# ESP_SPI.net
KiCad netlist of a schematic drawn in EAGLE
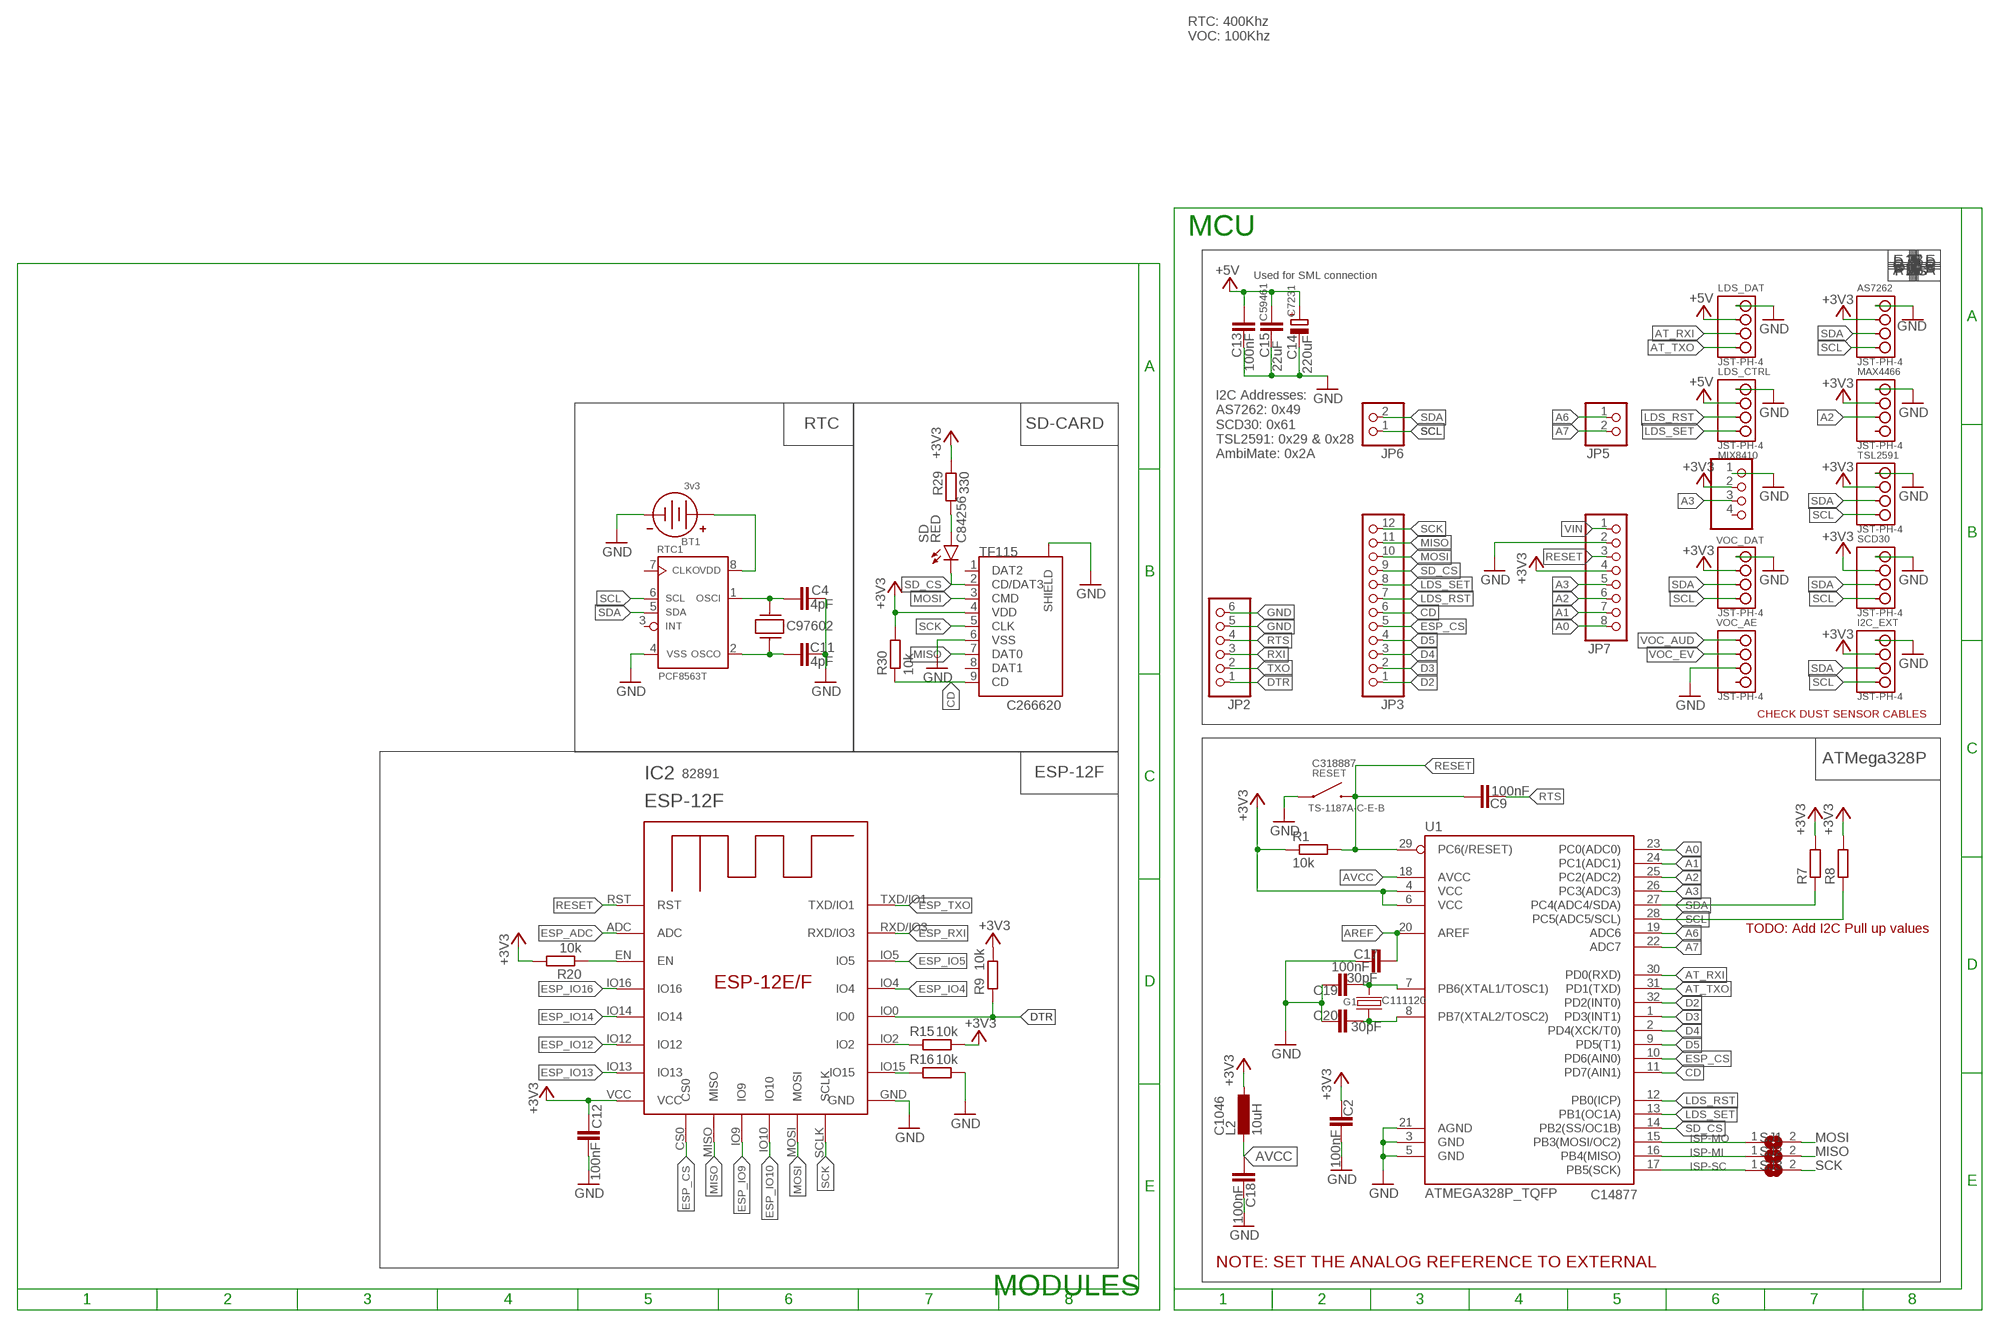
[diagram p0: schematic, sheet 1, part 1 of 2]
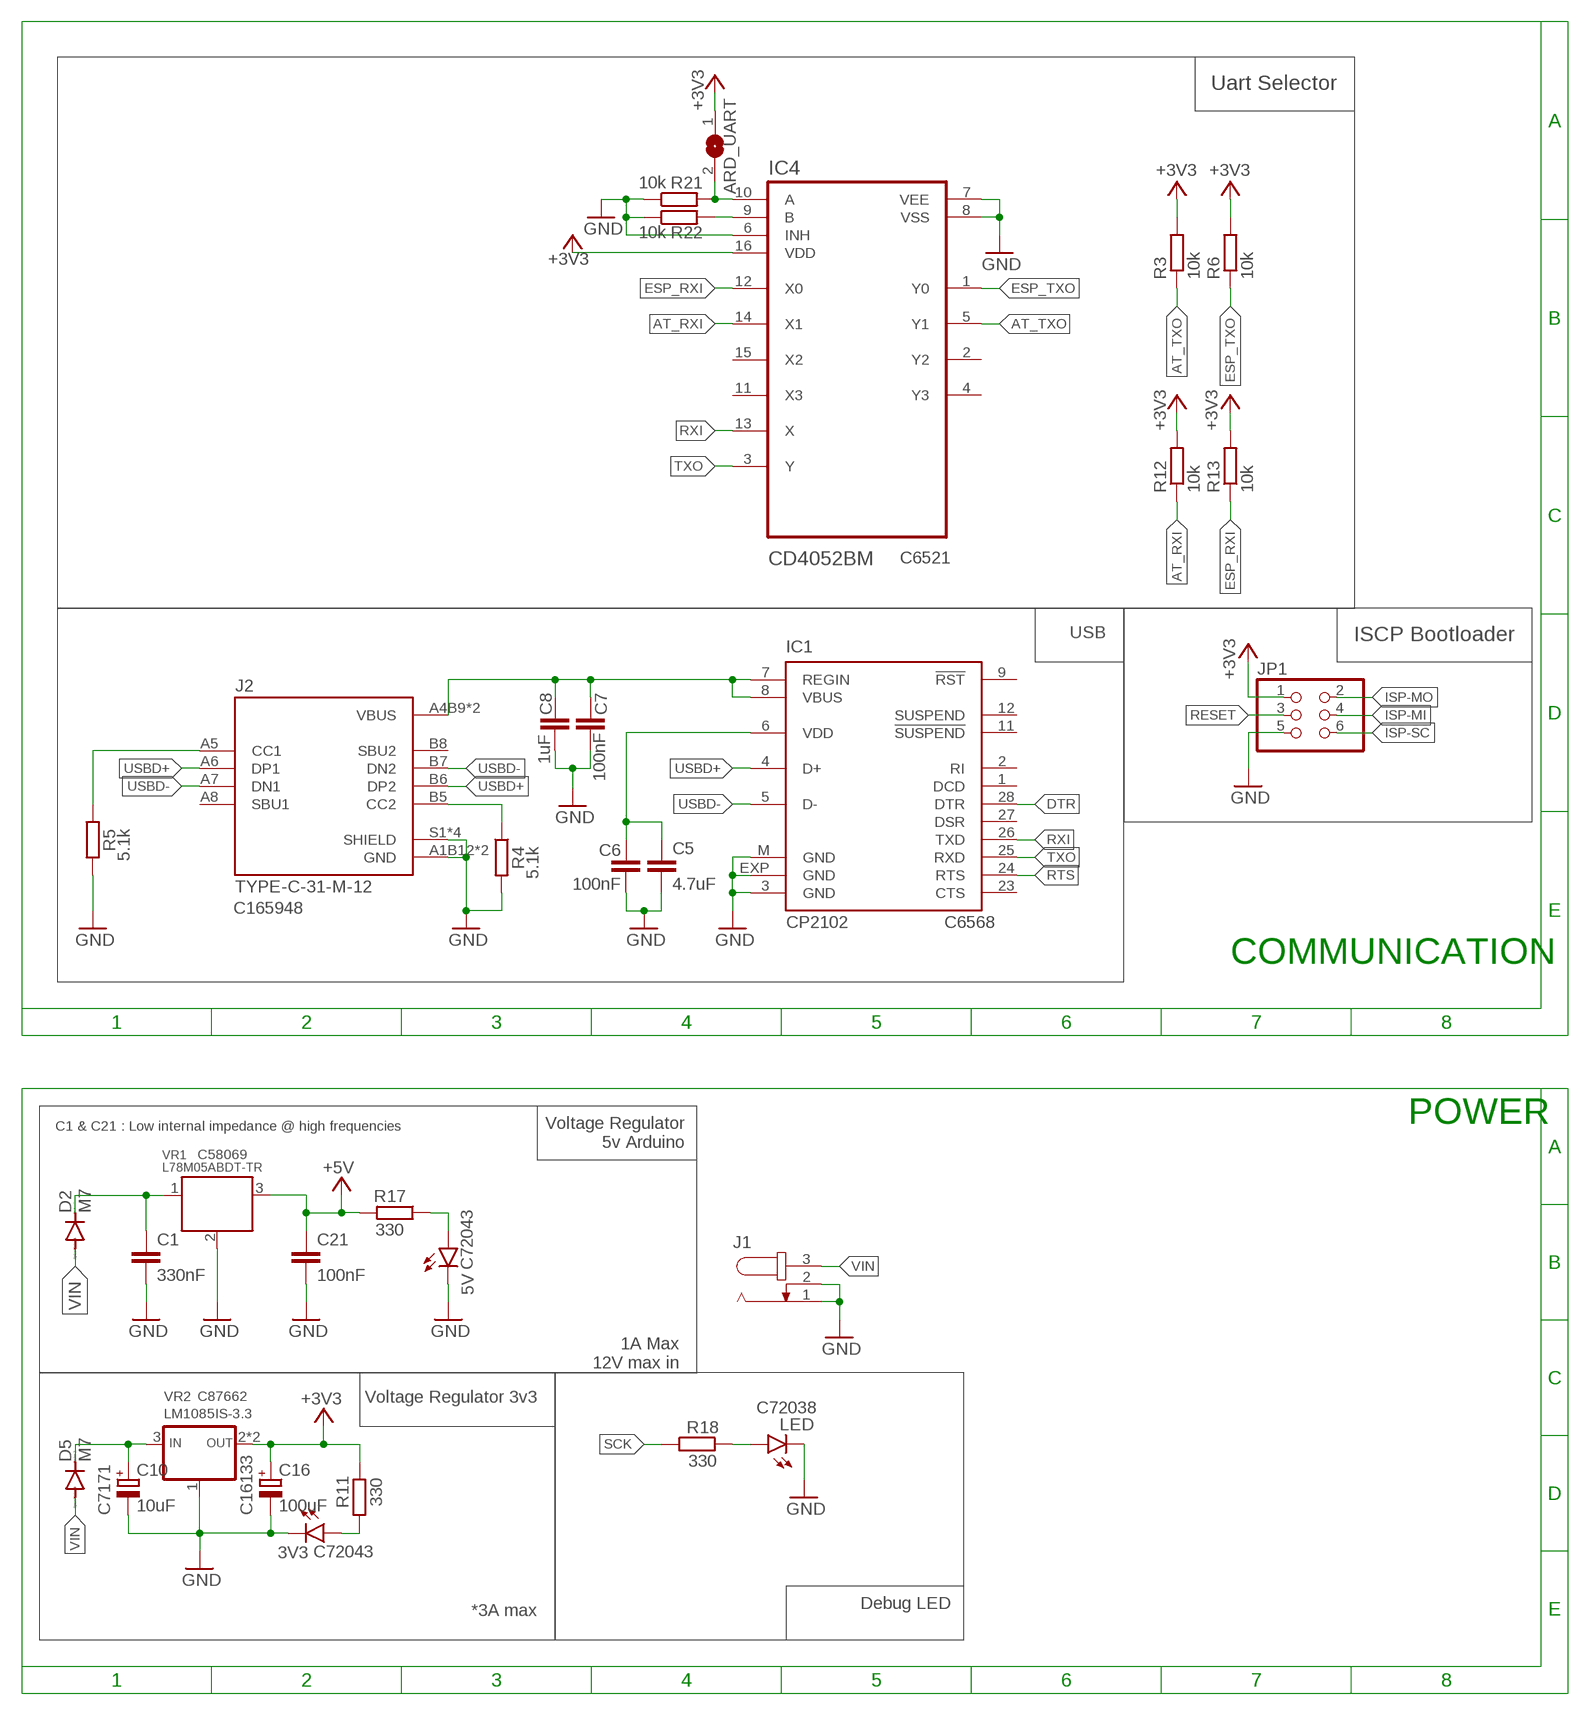
[diagram p1: schematic, sheet 1, part 2 of 2]

(export (version "E")
  (design (tool "Eeschema 10.0.6"))
  (components
    (comp (ref "3V3")
      (value "C72043")
      (footprint "eagle-import:CHIPLED_0603")
      (fields (field (name "PTNR") "C72043"))
      (libsource (lib "eagle-import") (part "LEDCHIPLED_0603"))
    )
    (comp (ref "5V")
      (value "C72043")
      (footprint "eagle-import:CHIPLED_0603")
      (fields (field (name "PTNR") "C72043"))
      (libsource (lib "eagle-import") (part "LEDCHIPLED_0603"))
    )
    (comp (ref "ARD_UART")
      (value "SJ")
      (footprint "eagle-import:SJ")
      (libsource (lib "eagle-import") (part "SJ"))
    )
    (comp (ref "AS7262")
      (value "JST-PH-4")
      (footprint "eagle-import:JST-PH-4")
      (libsource (lib "eagle-import") (part "JST-PH-4"))
    )
    (comp (ref "BT1")
      (value "3v3")
      (footprint "eagle-import:CH29-2032LF")
      (libsource (lib "eagle-import") (part "CH29-2032LF"))
    )
    (comp (ref "C1")
      (value "330nF")
      (footprint "eagle-import:C0805")
      (libsource (lib "eagle-import") (part "C-EUC0805"))
    )
    (comp (ref "C2")
      (value "100nF")
      (footprint "eagle-import:C0402")
      (libsource (lib "eagle-import") (part "C-EUC0402"))
    )
    (comp (ref "C4")
      (value "4pF")
      (footprint "eagle-import:C0402")
      (libsource (lib "eagle-import") (part "C-EUC0402"))
    )
    (comp (ref "C5")
      (value "4.7uF")
      (footprint "eagle-import:C0402")
      (libsource (lib "eagle-import") (part "C-EUC0402"))
    )
    (comp (ref "C6")
      (value "100nF")
      (footprint "eagle-import:C0402")
      (libsource (lib "eagle-import") (part "C-EUC0402"))
    )
    (comp (ref "C7")
      (value "100nF")
      (footprint "eagle-import:C0402")
      (libsource (lib "eagle-import") (part "C-EUC0402"))
    )
    (comp (ref "C8")
      (value "1uF")
      (footprint "eagle-import:C0402")
      (libsource (lib "eagle-import") (part "C-EUC0402"))
    )
    (comp (ref "C9")
      (value "100nF")
      (footprint "eagle-import:C0402")
      (libsource (lib "eagle-import") (part "C-EUC0402"))
    )
    (comp (ref "C10")
      (value "10uF")
      (footprint "eagle-import:A_3216-18R")
      (fields (field (name "PTRNR") "C7171"))
      (libsource (lib "eagle-import") (part "CPOL-EUA/3216-18R"))
    )
    (comp (ref "C11")
      (value "4pF")
      (footprint "eagle-import:C0402")
      (libsource (lib "eagle-import") (part "C-EUC0402"))
    )
    (comp (ref "C12")
      (value "100nF")
      (footprint "eagle-import:C0402")
      (libsource (lib "eagle-import") (part "C-EUC0402"))
    )
    (comp (ref "C13")
      (value "100nF")
      (footprint "eagle-import:C0402")
      (libsource (lib "eagle-import") (part "C-EUC0402"))
    )
    (comp (ref "C14")
      (value "220uF")
      (footprint "eagle-import:A_3216-18R")
      (fields (field (name "PTRNR") "C7231"))
      (libsource (lib "eagle-import") (part "CPOL-EUA/3216-18R"))
    )
    (comp (ref "C15")
      (value "22uF")
      (footprint "eagle-import:C0603")
      (fields (field (name "PTRNR") "C59461"))
      (libsource (lib "eagle-import") (part "C-EUC0603"))
    )
    (comp (ref "C16")
      (value "100uF")
      (footprint "eagle-import:B_3528-21W")
      (fields (field (name "PTRNR") "C16133"))
      (libsource (lib "eagle-import") (part "CPOL-EUB/3528-21W"))
    )
    (comp (ref "C17")
      (value "100nF")
      (footprint "eagle-import:C0402")
      (libsource (lib "eagle-import") (part "C-EUC0402"))
    )
    (comp (ref "C18")
      (value "100nF")
      (footprint "eagle-import:C0402")
      (libsource (lib "eagle-import") (part "C-EUC0402"))
    )
    (comp (ref "C19")
      (value "30pF")
      (footprint "eagle-import:C0402")
      (libsource (lib "eagle-import") (part "C-EUC0402"))
    )
    (comp (ref "C20")
      (value "30pF")
      (footprint "eagle-import:C0402")
      (libsource (lib "eagle-import") (part "C-EUC0402"))
    )
    (comp (ref "C21")
      (value "100nF")
      (footprint "eagle-import:C0402")
      (libsource (lib "eagle-import") (part "C-EUC0402"))
    )
    (comp (ref "D2")
      (value "M7")
      (footprint "eagle-import:DO-214AC")
      (libsource (lib "eagle-import") (part "M7DO-214AC"))
    )
    (comp (ref "D5")
      (value "M7")
      (footprint "eagle-import:DO-214AC")
      (libsource (lib "eagle-import") (part "M7DO-214AC"))
    )
    (comp (ref "G1")
      (value "8Mhz")
      (footprint "eagle-import:7A08000008")
      (fields (field (name "PTRNR") "C111120"))
      (libsource (lib "eagle-import") (part "7A08000008"))
    )
    (comp (ref "G2")
      (value "32.768KHZ")
      (footprint "eagle-import:32.768KHZ")
      (fields (field (name "PTRNR") "C97602"))
      (libsource (lib "eagle-import") (part "32.768KHZ"))
    )
    (comp (ref "I2C_EXT")
      (value "JST-PH-4")
      (footprint "eagle-import:JST-PH-4")
      (libsource (lib "eagle-import") (part "JST-PH-4"))
    )
    (comp (ref "IC1")
      (value "CP2102")
      (footprint "eagle-import:MLP28")
      (fields
        (field (name "MF") "FARNELL")
        (field (name "MPN") "CP2102-GM")
        (field (name "PTRNR") "C6568")
        (field (name "PTRNR_1") "C6568")
      )
      (libsource (lib "eagle-import") (part "CP2102"))
    )
    (comp (ref "IC2")
      (value "ESP-12F")
      (footprint "eagle-import:ESP-12E")
      (fields (field (name "PTRNR") "82891"))
      (libsource (lib "eagle-import") (part "ESP-12F"))
    )
    (comp (ref "IC4")
      (value "CD4052BM")
      (footprint "eagle-import:SOIC127P600X175-16N")
      (fields
        (field (name "MF") "Texas Instruments")
        (field (name "PTRNR") "C6521")
        (field (name "PTRNR_1") "C6521")
      )
      (libsource (lib "eagle-import") (part "CD4052BM"))
    )
    (comp (ref "J1")
      (value "JACK-PLUG1")
      (footprint "eagle-import:SPC4078")
      (libsource (lib "eagle-import") (part "JACK-PLUG1"))
    )
    (comp (ref "J2")
      (value "TYPE-C-31-M-12")
      (footprint "eagle-import:HRO_TYPE-C-31-M-12")
      (fields
        (field (name "MF") "HRO Electronics Co., Ltd.")
        (field (name "PTRNR") "C165948")
        (field (name "PTRNR_1") "C165948")
      )
      (libsource (lib "eagle-import") (part "TYPE-C-31-M-12"))
    )
    (comp (ref "JP1")
      (value "PINHD-2X3")
      (footprint "eagle-import:2X03")
      (libsource (lib "eagle-import") (part "PINHD-2X3"))
    )
    (comp (ref "JP2")
      (value "PINHD-1X6/90")
      (footprint "eagle-import:1X06_90")
      (libsource (lib "eagle-import") (part "PINHD-1X6/90"))
    )
    (comp (ref "JP3")
      (value "PINHD-1X12")
      (footprint "eagle-import:1X12")
      (libsource (lib "eagle-import") (part "PINHD-1X12"))
    )
    (comp (ref "JP5")
      (value "PINHD-1X2/90")
      (footprint "eagle-import:1X02_90")
      (libsource (lib "eagle-import") (part "PINHD-1X2/90"))
    )
    (comp (ref "JP6")
      (value "PINHD-1X2/90")
      (footprint "eagle-import:1X02_90")
      (libsource (lib "eagle-import") (part "PINHD-1X2/90"))
    )
    (comp (ref "JP7")
      (value "PINHD-1X8")
      (footprint "eagle-import:1X08")
      (libsource (lib "eagle-import") (part "PINHD-1X8"))
    )
    (comp (ref "L2")
      (value "10uH")
      (footprint "eagle-import:L2012C")
      (fields (field (name "PRTNR") "C1046"))
      (libsource (lib "eagle-import") (part "L-EUL2012C"))
    )
    (comp (ref "LDS_CTRL")
      (value "JST-PH-4")
      (footprint "eagle-import:JST-PH-4")
      (libsource (lib "eagle-import") (part "JST-PH-4"))
    )
    (comp (ref "LDS_DAT")
      (value "JST-PH-4")
      (footprint "eagle-import:JST-PH-4")
      (libsource (lib "eagle-import") (part "JST-PH-4"))
    )
    (comp (ref "LED")
      (value "YELLOW")
      (footprint "eagle-import:CHIPLED_0603")
      (fields (field (name "PTRNR") "C72038"))
      (libsource (lib "eagle-import") (part "LEDCHIPLED_0603"))
    )
    (comp (ref "MAX4466")
      (value "JST-PH-4")
      (footprint "eagle-import:JST-PH-4")
      (libsource (lib "eagle-import") (part "JST-PH-4"))
    )
    (comp (ref "MIX8410")
      (value "PINHD-1X4")
      (footprint "eagle-import:1X04")
      (libsource (lib "eagle-import") (part "PINHD-1X4"))
    )
    (comp (ref "R1")
      (value "10k")
      (footprint "eagle-import:R0402")
      (libsource (lib "eagle-import") (part "R-EU_R0402"))
    )
    (comp (ref "R3")
      (value "10k")
      (footprint "eagle-import:R0402")
      (libsource (lib "eagle-import") (part "R-EU_R0402"))
    )
    (comp (ref "R4")
      (value "5.1k")
      (footprint "eagle-import:R0402")
      (libsource (lib "eagle-import") (part "R-EU_R0402"))
    )
    (comp (ref "R5")
      (value "5.1k")
      (footprint "eagle-import:R0402")
      (libsource (lib "eagle-import") (part "R-EU_R0402"))
    )
    (comp (ref "R6")
      (value "10k")
      (footprint "eagle-import:R0402")
      (libsource (lib "eagle-import") (part "R-EU_R0402"))
    )
    (comp (ref "R7")
      (value "R-EU_R0402")
      (footprint "eagle-import:R0402")
      (libsource (lib "eagle-import") (part "R-EU_R0402"))
    )
    (comp (ref "R8")
      (value "R-EU_R0402")
      (footprint "eagle-import:R0402")
      (libsource (lib "eagle-import") (part "R-EU_R0402"))
    )
    (comp (ref "R9")
      (value "10k")
      (footprint "eagle-import:R0402")
      (libsource (lib "eagle-import") (part "R-EU_R0402"))
    )
    (comp (ref "R11")
      (value "330")
      (footprint "eagle-import:M0805")
      (libsource (lib "eagle-import") (part "R-EU_M0805"))
    )
    (comp (ref "R12")
      (value "10k")
      (footprint "eagle-import:R0402")
      (libsource (lib "eagle-import") (part "R-EU_R0402"))
    )
    (comp (ref "R13")
      (value "10k")
      (footprint "eagle-import:R0402")
      (libsource (lib "eagle-import") (part "R-EU_R0402"))
    )
    (comp (ref "R15")
      (value "10k")
      (footprint "eagle-import:R0402")
      (libsource (lib "eagle-import") (part "R-EU_R0402"))
    )
    (comp (ref "R16")
      (value "10k")
      (footprint "eagle-import:R0402")
      (libsource (lib "eagle-import") (part "R-EU_R0402"))
    )
    (comp (ref "R17")
      (value "330")
      (footprint "eagle-import:M0805")
      (libsource (lib "eagle-import") (part "R-EU_M0805"))
    )
    (comp (ref "R18")
      (value "330")
      (footprint "eagle-import:M0805")
      (libsource (lib "eagle-import") (part "R-EU_M0805"))
    )
    (comp (ref "R20")
      (value "10k")
      (footprint "eagle-import:R0402")
      (libsource (lib "eagle-import") (part "R-EU_R0402"))
    )
    (comp (ref "R21")
      (value "10k")
      (footprint "eagle-import:R0402")
      (libsource (lib "eagle-import") (part "R-EU_R0402"))
    )
    (comp (ref "R22")
      (value "10k")
      (footprint "eagle-import:R0402")
      (libsource (lib "eagle-import") (part "R-EU_R0402"))
    )
    (comp (ref "R29")
      (value "330")
      (footprint "eagle-import:R0402")
      (libsource (lib "eagle-import") (part "R-EU_R0402"))
    )
    (comp (ref "R30")
      (value "10k")
      (footprint "eagle-import:R0402")
      (libsource (lib "eagle-import") (part "R-EU_R0402"))
    )
    (comp (ref "RESET")
      (value "TS-1187A-C-E-B")
      (footprint "eagle-import:TS-1187A-C-E-B")
      (fields (field (name "PRTNR") "C318887") (field (name "PRTNR_1") "C318887"))
      (libsource (lib "eagle-import") (part "TS-1187A-C-E-B"))
    )
    (comp (ref "RTC1")
      (value "PCF8563T")
      (footprint "eagle-import:SOIC8")
      (libsource (lib "eagle-import") (part "PCF8563T"))
    )
    (comp (ref "SCD30")
      (value "JST-PH-4")
      (footprint "eagle-import:JST-PH-4")
      (libsource (lib "eagle-import") (part "JST-PH-4"))
    )
    (comp (ref "SD")
      (value "RED")
      (footprint "eagle-import:CHIPLED_0805")
      (fields (field (name "PTRNR") "C84256"))
      (libsource (lib "eagle-import") (part "LEDCHIPLED_0805"))
    )
    (comp (ref "SJ1") (value "SJ") (footprint "eagle-import:SJ") (libsource (lib "eagle-import") (part "SJ")))
    (comp (ref "SJ2") (value "SJ") (footprint "eagle-import:SJ") (libsource (lib "eagle-import") (part "SJ")))
    (comp (ref "SJ3") (value "SJ") (footprint "eagle-import:SJ") (libsource (lib "eagle-import") (part "SJ")))
    (comp (ref "TF115")
      (value "TF-115")
      (footprint "eagle-import:TF-115")
      (fields (field (name "PTRNR") "C266620"))
      (libsource (lib "eagle-import") (part "TF-115"))
    )
    (comp (ref "TSL2591")
      (value "JST-PH-4")
      (footprint "eagle-import:JST-PH-4")
      (libsource (lib "eagle-import") (part "JST-PH-4"))
    )
    (comp (ref "U1")
      (value "ATMEGA328P_TQFP")
      (footprint "eagle-import:TQFP32-08")
      (fields (field (name "PTRNR") "C14877"))
      (libsource (lib "eagle-import") (part "ATMEGA328P_TQFP"))
    )
    (comp (ref "VOC_AE")
      (value "JST-PH-4")
      (footprint "eagle-import:JST-PH-4")
      (libsource (lib "eagle-import") (part "JST-PH-4"))
    )
    (comp (ref "VOC_DAT")
      (value "JST-PH-4")
      (footprint "eagle-import:JST-PH-4")
      (libsource (lib "eagle-import") (part "JST-PH-4"))
    )
    (comp (ref "VR1")
      (value "L78M05ABDT-TR")
      (footprint "eagle-import:DPAK")
      (fields (field (name "PTRNR") "C58069"))
      (libsource (lib "eagle-import") (part "L78M05ABDT-TR"))
    )
    (comp (ref "VR2")
      (value "LM1085IS-3.3")
      (footprint "eagle-import:TO263-3")
      (fields (field (name "PTRNR") "C87662") (field (name "PTRNR_1") "C87662"))
      (libsource (lib "eagle-import") (part "LM1085IS-3.3"))
    )
  )
  (nets
    (net (code "1") (name "+3V3") (class "Default")
      (node (ref "ARD_UART") (pin "1") (pinfunction "1_1") (pintype "passive"))
      (node (ref "AS7262") (pin "P2") (pinfunction "2_P2") (pintype "bidirectional"))
      (node (ref "C12") (pin "1") (pinfunction "1_1") (pintype "passive"))
      (node (ref "C16") (pin "+") (pinfunction "+_+") (pintype "passive"))
      (node (ref "C2") (pin "2") (pinfunction "2_2") (pintype "passive"))
      (node (ref "I2C_EXT") (pin "P2") (pinfunction "2_P2") (pintype "bidirectional"))
      (node (ref "IC2") (pin "VCC") (pinfunction "VCC_VCC") (pintype "power_in"))
      (node (ref "IC4") (pin "16") (pinfunction "VDD_16") (pintype "input"))
      (node (ref "JP1") (pin "1") (pinfunction "1_1") (pintype "passive"))
      (node (ref "JP7") (pin "4") (pinfunction "4_4") (pintype "passive"))
      (node (ref "L2") (pin "1") (pinfunction "1_1") (pintype "passive"))
      (node (ref "MAX4466") (pin "P2") (pinfunction "2_P2") (pintype "bidirectional"))
      (node (ref "MIX8410") (pin "2") (pinfunction "2_2") (pintype "passive"))
      (node (ref "R1") (pin "1") (pinfunction "1_1") (pintype "passive"))
      (node (ref "R11") (pin "2") (pinfunction "2_2") (pintype "passive"))
      (node (ref "R12") (pin "2") (pinfunction "2_2") (pintype "passive"))
      (node (ref "R13") (pin "2") (pinfunction "2_2") (pintype "passive"))
      (node (ref "R15") (pin "1") (pinfunction "1_1") (pintype "passive"))
      (node (ref "R20") (pin "2") (pinfunction "2_2") (pintype "passive"))
      (node (ref "R29") (pin "2") (pinfunction "2_2") (pintype "passive"))
      (node (ref "R3") (pin "2") (pinfunction "2_2") (pintype "passive"))
      (node (ref "R30") (pin "2") (pinfunction "2_2") (pintype "passive"))
      (node (ref "R6") (pin "2") (pinfunction "2_2") (pintype "passive"))
      (node (ref "R7") (pin "2") (pinfunction "2_2") (pintype "passive"))
      (node (ref "R8") (pin "2") (pinfunction "2_2") (pintype "passive"))
      (node (ref "R9") (pin "1") (pinfunction "1_1") (pintype "passive"))
      (node (ref "SCD30") (pin "P2") (pinfunction "2_P2") (pintype "bidirectional"))
      (node (ref "TF115") (pin "4") (pinfunction "VDD_4") (pintype "bidirectional"))
      (node (ref "TSL2591") (pin "P2") (pinfunction "2_P2") (pintype "bidirectional"))
      (node (ref "U1") (pin "4") (pinfunction "VCC_4") (pintype "bidirectional"))
      (node (ref "U1") (pin "6") (pinfunction "VCC_6") (pintype "bidirectional"))
      (node (ref "VOC_DAT") (pin "P2") (pinfunction "2_P2") (pintype "bidirectional"))
      (node (ref "VR2") (pin "2") (pinfunction "OUT_2") (pintype "output"))
      (node (ref "VR2") (pin "TAB") (pinfunction "OUT_TAB") (pintype "output"))
    )
    (net (code "2") (name "+5V") (class "Default")
      (node (ref "C13") (pin "1") (pinfunction "1_1") (pintype "passive"))
      (node (ref "C14") (pin "+") (pinfunction "+_+") (pintype "passive"))
      (node (ref "C15") (pin "1") (pinfunction "1_1") (pintype "passive"))
      (node (ref "C21") (pin "1") (pinfunction "1_1") (pintype "passive"))
      (node (ref "LDS_CTRL") (pin "P2") (pinfunction "2_P2") (pintype "bidirectional"))
      (node (ref "LDS_DAT") (pin "P2") (pinfunction "2_P2") (pintype "bidirectional"))
      (node (ref "R17") (pin "2") (pinfunction "2_2") (pintype "passive"))
      (node (ref "VR1") (pin "3") (pinfunction "VO_3") (pintype "output"))
    )
    (net (code "3") (name "A0") (class "Default")
      (node (ref "JP7") (pin "8") (pinfunction "8_8") (pintype "passive"))
      (node (ref "U1") (pin "23") (pinfunction "PC0(ADC0)_23") (pintype "bidirectional"))
    )
    (net (code "4") (name "A1") (class "Default")
      (node (ref "JP7") (pin "7") (pinfunction "7_7") (pintype "passive"))
      (node (ref "U1") (pin "24") (pinfunction "PC1(ADC1)_24") (pintype "bidirectional"))
    )
    (net (code "5") (name "A2") (class "Default")
      (node (ref "JP7") (pin "6") (pinfunction "6_6") (pintype "passive"))
      (node (ref "MAX4466") (pin "P3") (pinfunction "3_P3") (pintype "bidirectional"))
      (node (ref "U1") (pin "25") (pinfunction "PC2(ADC2)_25") (pintype "bidirectional"))
    )
    (net (code "6") (name "A3") (class "Default")
      (node (ref "JP7") (pin "5") (pinfunction "5_5") (pintype "passive"))
      (node (ref "MIX8410") (pin "3") (pinfunction "3_3") (pintype "passive"))
      (node (ref "U1") (pin "26") (pinfunction "PC3(ADC3)_26") (pintype "bidirectional"))
    )
    (net (code "7") (name "A6") (class "Default")
      (node (ref "JP5") (pin "1") (pinfunction "1_1") (pintype "passive"))
      (node (ref "U1") (pin "19") (pinfunction "ADC6_19") (pintype "bidirectional"))
    )
    (net (code "8") (name "A7") (class "Default")
      (node (ref "JP5") (pin "2") (pinfunction "2_2") (pintype "passive"))
      (node (ref "U1") (pin "22") (pinfunction "ADC7_22") (pintype "bidirectional"))
    )
    (net (code "9") (name "AREF") (class "Default")
      (node (ref "C17") (pin "1") (pinfunction "1_1") (pintype "passive"))
      (node (ref "U1") (pin "20") (pinfunction "AREF_20") (pintype "bidirectional"))
    )
    (net (code "10") (name "AT_RXI") (class "Default")
      (node (ref "IC4") (pin "14") (pinfunction "X1_14") (pintype "bidirectional"))
      (node (ref "LDS_DAT") (pin "P3") (pinfunction "3_P3") (pintype "bidirectional"))
      (node (ref "R12") (pin "1") (pinfunction "1_1") (pintype "passive"))
      (node (ref "U1") (pin "30") (pinfunction "PD0(RXD)_30") (pintype "bidirectional"))
    )
    (net (code "11") (name "AT_TXO") (class "Default")
      (node (ref "IC4") (pin "5") (pinfunction "Y1_5") (pintype "bidirectional"))
      (node (ref "LDS_DAT") (pin "P4") (pinfunction "4_P4") (pintype "bidirectional"))
      (node (ref "R3") (pin "1") (pinfunction "1_1") (pintype "passive"))
      (node (ref "U1") (pin "31") (pinfunction "PD1(TXD)_31") (pintype "bidirectional"))
    )
    (net (code "12") (name "AVCC") (class "Default")
      (node (ref "C18") (pin "2") (pinfunction "2_2") (pintype "passive"))
      (node (ref "L2") (pin "2") (pinfunction "2_2") (pintype "passive"))
      (node (ref "U1") (pin "18") (pinfunction "AVCC_18") (pintype "bidirectional"))
    )
    (net (code "13") (name "CD") (class "Default")
      (node (ref "JP3") (pin "6") (pinfunction "6_6") (pintype "passive"))
      (node (ref "R30") (pin "1") (pinfunction "1_1") (pintype "passive"))
      (node (ref "TF115") (pin "9") (pinfunction "CD_9") (pintype "bidirectional"))
      (node (ref "U1") (pin "11") (pinfunction "PD7(AIN1)_11") (pintype "bidirectional"))
    )
    (net (code "14") (name "D2") (class "Default")
      (node (ref "JP3") (pin "1") (pinfunction "1_1") (pintype "passive"))
      (node (ref "U1") (pin "32") (pinfunction "PD2(INT0)_32") (pintype "bidirectional"))
    )
    (net (code "15") (name "D3") (class "Default")
      (node (ref "JP3") (pin "2") (pinfunction "2_2") (pintype "passive"))
      (node (ref "U1") (pin "1") (pinfunction "PD3(INT1)_1") (pintype "bidirectional"))
    )
    (net (code "16") (name "D4") (class "Default")
      (node (ref "JP3") (pin "3") (pinfunction "3_3") (pintype "passive"))
      (node (ref "U1") (pin "2") (pinfunction "PD4(XCK/T0)_2") (pintype "bidirectional"))
    )
    (net (code "17") (name "D5") (class "Default")
      (node (ref "JP3") (pin "4") (pinfunction "4_4") (pintype "passive"))
      (node (ref "U1") (pin "9") (pinfunction "PD5(T1)_9") (pintype "bidirectional"))
    )
    (net (code "18") (name "DTR") (class "Default")
      (node (ref "IC1") (pin "28") (pinfunction "DTR_28") (pintype "output"))
      (node (ref "IC2") (pin "IO0") (pinfunction "IO0_IO0") (pintype "bidirectional"))
      (node (ref "JP2") (pin "1") (pinfunction "1_1") (pintype "passive"))
      (node (ref "R9") (pin "2") (pinfunction "2_2") (pintype "passive"))
    )
    (net (code "19") (name "ESP_ADC") (class "Default")
      (node (ref "IC2") (pin "ADC") (pinfunction "ADC_ADC") (pintype "bidirectional"))
    )
    (net (code "20") (name "ESP_CS") (class "Default")
      (node (ref "IC2") (pin "CS0") (pinfunction "CS0_CS0") (pintype "bidirectional"))
      (node (ref "JP3") (pin "5") (pinfunction "5_5") (pintype "passive"))
      (node (ref "U1") (pin "10") (pinfunction "PD6(AIN0)_10") (pintype "bidirectional"))
    )
    (net (code "21") (name "ESP_IO4") (class "Default")
      (node (ref "IC2") (pin "IO4") (pinfunction "IO4_IO4") (pintype "bidirectional"))
    )
    (net (code "22") (name "ESP_IO5") (class "Default")
      (node (ref "IC2") (pin "IO5") (pinfunction "IO5_IO5") (pintype "bidirectional"))
    )
    (net (code "23") (name "ESP_IO9") (class "Default")
      (node (ref "IC2") (pin "IO9") (pinfunction "IO9_IO9") (pintype "bidirectional"))
    )
    (net (code "24") (name "ESP_IO10") (class "Default")
      (node (ref "IC2") (pin "IO10") (pinfunction "IO10_IO10") (pintype "bidirectional"))
    )
    (net (code "25") (name "ESP_IO12") (class "Default")
      (node (ref "IC2") (pin "IO12") (pinfunction "IO12_IO12") (pintype "bidirectional"))
    )
    (net (code "26") (name "ESP_IO13") (class "Default")
      (node (ref "IC2") (pin "IO13") (pinfunction "IO13_IO13") (pintype "bidirectional"))
    )
    (net (code "27") (name "ESP_IO14") (class "Default")
      (node (ref "IC2") (pin "IO14") (pinfunction "IO14_IO14") (pintype "bidirectional"))
    )
    (net (code "28") (name "ESP_IO16") (class "Default")
      (node (ref "IC2") (pin "IO16") (pinfunction "IO16_IO16") (pintype "bidirectional"))
    )
    (net (code "29") (name "ESP_RXI") (class "Default")
      (node (ref "IC2") (pin "RXD/IO3") (pinfunction "RXD/IO3_RXD/IO3") (pintype "bidirectional"))
      (node (ref "IC4") (pin "12") (pinfunction "X0_12") (pintype "bidirectional"))
      (node (ref "R13") (pin "1") (pinfunction "1_1") (pintype "passive"))
    )
    (net (code "30") (name "ESP_TXO") (class "Default")
      (node (ref "IC2") (pin "TXD/IO1") (pinfunction "TXD/IO1_TXD/IO1") (pintype "bidirectional"))
      (node (ref "IC4") (pin "1") (pinfunction "Y0_1") (pintype "bidirectional"))
      (node (ref "R6") (pin "1") (pinfunction "1_1") (pintype "passive"))
    )
    (net (code "31") (name "GND") (class "Default")
      (node (ref "3V3") (pin "C") (pinfunction "C_C") (pintype "passive"))
      (node (ref "5V") (pin "C") (pinfunction "C_C") (pintype "passive"))
      (node (ref "AS7262") (pin "P1") (pinfunction "1_P1") (pintype "bidirectional"))
      (node (ref "BT1") (pin "GND") (pinfunction "GND_GND") (pintype "power_in"))
      (node (ref "C1") (pin "2") (pinfunction "2_2") (pintype "passive"))
      (node (ref "C10") (pin "-") (pinfunction "-_-") (pintype "passive"))
      (node (ref "C11") (pin "2") (pinfunction "2_2") (pintype "passive"))
      (node (ref "C12") (pin "2") (pinfunction "2_2") (pintype "passive"))
      (node (ref "C13") (pin "2") (pinfunction "2_2") (pintype "passive"))
      (node (ref "C14") (pin "-") (pinfunction "-_-") (pintype "passive"))
      (node (ref "C15") (pin "2") (pinfunction "2_2") (pintype "passive"))
      (node (ref "C16") (pin "-") (pinfunction "-_-") (pintype "passive"))
      (node (ref "C17") (pin "2") (pinfunction "2_2") (pintype "passive"))
      (node (ref "C18") (pin "1") (pinfunction "1_1") (pintype "passive"))
      (node (ref "C19") (pin "2") (pinfunction "2_2") (pintype "passive"))
      (node (ref "C2") (pin "1") (pinfunction "1_1") (pintype "passive"))
      (node (ref "C20") (pin "2") (pinfunction "2_2") (pintype "passive"))
      (node (ref "C21") (pin "2") (pinfunction "2_2") (pintype "passive"))
      (node (ref "C4") (pin "2") (pinfunction "2_2") (pintype "passive"))
      (node (ref "C5") (pin "2") (pinfunction "2_2") (pintype "passive"))
      (node (ref "C6") (pin "2") (pinfunction "2_2") (pintype "passive"))
      (node (ref "C7") (pin "2") (pinfunction "2_2") (pintype "passive"))
      (node (ref "C8") (pin "2") (pinfunction "2_2") (pintype "passive"))
      (node (ref "I2C_EXT") (pin "P1") (pinfunction "1_P1") (pintype "bidirectional"))
      (node (ref "IC1") (pin "3") (pinfunction "GND_3") (pintype "power_in"))
      (node (ref "IC1") (pin "EXP") (pinfunction "GND_EXP") (pintype "power_in"))
      (node (ref "IC1") (pin "M") (pinfunction "GND_M") (pintype "power_in"))
      (node (ref "IC2") (pin "GND") (pinfunction "GND_GND") (pintype "power_in"))
      (node (ref "IC4") (pin "6") (pinfunction "INH_6") (pintype "input"))
      (node (ref "IC4") (pin "7") (pinfunction "VEE_7") (pintype "power_in"))
      (node (ref "IC4") (pin "8") (pinfunction "VSS_8") (pintype "power_in"))
      (node (ref "J1") (pin "1") (pinfunction "1_1") (pintype "passive"))
      (node (ref "J1") (pin "2") (pinfunction "2_2") (pintype "passive"))
      (node (ref "J2") (pin "A1B12") (pinfunction "GND_A1B12") (pintype "power_in"))
      (node (ref "J2") (pin "B1A12") (pinfunction "GND_B1A12") (pintype "power_in"))
      (node (ref "J2") (pin "S1") (pinfunction "SHIELD_S1") (pintype "passive"))
      (node (ref "J2") (pin "S2") (pinfunction "SHIELD_S2") (pintype "passive"))
      (node (ref "J2") (pin "S3") (pinfunction "SHIELD_S3") (pintype "passive"))
      (node (ref "J2") (pin "S4") (pinfunction "SHIELD_S4") (pintype "passive"))
      (node (ref "JP1") (pin "5") (pinfunction "5_5") (pintype "passive"))
      (node (ref "JP2") (pin "5") (pinfunction "5_5") (pintype "passive"))
      (node (ref "JP2") (pin "6") (pinfunction "6_6") (pintype "passive"))
      (node (ref "JP7") (pin "2") (pinfunction "2_2") (pintype "passive"))
      (node (ref "LDS_CTRL") (pin "P1") (pinfunction "1_P1") (pintype "bidirectional"))
      (node (ref "LDS_DAT") (pin "P1") (pinfunction "1_P1") (pintype "bidirectional"))
      (node (ref "LED") (pin "C") (pinfunction "C_C") (pintype "passive"))
      (node (ref "MAX4466") (pin "P1") (pinfunction "1_P1") (pintype "bidirectional"))
      (node (ref "MIX8410") (pin "1") (pinfunction "1_1") (pintype "passive"))
      (node (ref "R16") (pin "1") (pinfunction "1_1") (pintype "passive"))
      (node (ref "R21") (pin "1") (pinfunction "1_1") (pintype "passive"))
      (node (ref "R22") (pin "1") (pinfunction "1_1") (pintype "passive"))
      (node (ref "R4") (pin "2") (pinfunction "2_2") (pintype "passive"))
      (node (ref "R5") (pin "2") (pinfunction "2_2") (pintype "passive"))
      (node (ref "RESET") (pin "A") (pinfunction "A_A") (pintype "bidirectional"))
      (node (ref "RESET") (pin "B") (pinfunction "A_B") (pintype "bidirectional"))
      (node (ref "RTC1") (pin "4") (pinfunction "VSS_4") (pintype "bidirectional"))
      (node (ref "SCD30") (pin "P1") (pinfunction "1_P1") (pintype "bidirectional"))
      (node (ref "TF115") (pin "10") (pinfunction "SHIELD_10") (pintype "bidirectional"))
      (node (ref "TF115") (pin "11") (pinfunction "SHIELD_11") (pintype "bidirectional"))
      (node (ref "TF115") (pin "12") (pinfunction "SHIELD_12") (pintype "bidirectional"))
      (node (ref "TF115") (pin "13") (pinfunction "SHIELD_13") (pintype "bidirectional"))
      (node (ref "TF115") (pin "6") (pinfunction "VSS_6") (pintype "bidirectional"))
      (node (ref "TSL2591") (pin "P1") (pinfunction "1_P1") (pintype "bidirectional"))
      (node (ref "U1") (pin "21") (pinfunction "AGND_21") (pintype "bidirectional"))
      (node (ref "U1") (pin "3") (pinfunction "GND_3") (pintype "bidirectional"))
      (node (ref "U1") (pin "5") (pinfunction "GND_5") (pintype "bidirectional"))
      (node (ref "VOC_AE") (pin "P3") (pinfunction "3_P3") (pintype "bidirectional"))
      (node (ref "VOC_DAT") (pin "P1") (pinfunction "1_P1") (pintype "bidirectional"))
      (node (ref "VR1") (pin "2") (pinfunction "GND_2") (pintype "output"))
      (node (ref "VR2") (pin "1") (pinfunction "ADJ_1") (pintype "bidirectional"))
    )
    (net (code "32") (name "ISP-MI") (class "Default")
      (node (ref "JP1") (pin "4") (pinfunction "4_4") (pintype "passive"))
      (node (ref "SJ2") (pin "1") (pinfunction "1_1") (pintype "passive"))
      (node (ref "U1") (pin "16") (pinfunction "PB4(MISO)_16") (pintype "bidirectional"))
    )
    (net (code "33") (name "ISP-MO") (class "Default")
      (node (ref "JP1") (pin "2") (pinfunction "2_2") (pintype "passive"))
      (node (ref "SJ1") (pin "1") (pinfunction "1_1") (pintype "passive"))
      (node (ref "U1") (pin "15") (pinfunction "PB3(MOSI/OC2)_15") (pintype "bidirectional"))
    )
    (net (code "34") (name "ISP-SC") (class "Default")
      (node (ref "JP1") (pin "6") (pinfunction "6_6") (pintype "passive"))
      (node (ref "SJ3") (pin "1") (pinfunction "1_1") (pintype "passive"))
      (node (ref "U1") (pin "17") (pinfunction "PB5(SCK)_17") (pintype "bidirectional"))
    )
    (net (code "35") (name "LDS_RST") (class "Default")
      (node (ref "JP3") (pin "7") (pinfunction "7_7") (pintype "passive"))
      (node (ref "LDS_CTRL") (pin "P3") (pinfunction "3_P3") (pintype "bidirectional"))
      (node (ref "U1") (pin "12") (pinfunction "PB0(ICP)_12") (pintype "bidirectional"))
    )
    (net (code "36") (name "LDS_SET") (class "Default")
      (node (ref "JP3") (pin "8") (pinfunction "8_8") (pintype "passive"))
      (node (ref "LDS_CTRL") (pin "P4") (pinfunction "4_P4") (pintype "bidirectional"))
      (node (ref "U1") (pin "13") (pinfunction "PB1(OC1A)_13") (pintype "bidirectional"))
    )
    (net (code "37") (name "MISO") (class "Default")
      (node (ref "IC2") (pin "MISO") (pinfunction "MISO_MISO") (pintype "bidirectional"))
      (node (ref "JP3") (pin "11") (pinfunction "11_11") (pintype "passive"))
      (node (ref "SJ2") (pin "2") (pinfunction "2_2") (pintype "passive"))
      (node (ref "TF115") (pin "7") (pinfunction "DAT0_7") (pintype "bidirectional"))
    )
    (net (code "38") (name "MOSI") (class "Default")
      (node (ref "IC2") (pin "MOSI") (pinfunction "MOSI_MOSI") (pintype "bidirectional"))
      (node (ref "JP3") (pin "10") (pinfunction "10_10") (pintype "passive"))
      (node (ref "SJ1") (pin "2") (pinfunction "2_2") (pintype "passive"))
      (node (ref "TF115") (pin "3") (pinfunction "CMD_3") (pintype "bidirectional"))
    )
    (net (code "39") (name "Net-(3V3-PadA)") (class "Default")
      (node (ref "3V3") (pin "A") (pinfunction "A_A") (pintype "passive"))
      (node (ref "R11") (pin "1") (pinfunction "1_1") (pintype "passive"))
    )
    (net (code "40") (name "Net-(5V-PadA)") (class "Default")
      (node (ref "5V") (pin "A") (pinfunction "A_A") (pintype "passive"))
      (node (ref "R17") (pin "1") (pinfunction "1_1") (pintype "passive"))
    )
    (net (code "41") (name "Net-(G1-XT1)") (class "Default")
      (node (ref "C19") (pin "1") (pinfunction "1_1") (pintype "passive"))
      (node (ref "G1") (pin "P$1") (pinfunction "XT1_P$1") (pintype "bidirectional"))
      (node (ref "U1") (pin "7") (pinfunction "PB6(XTAL1/TOSC1)_7") (pintype "bidirectional"))
    )
    (net (code "42") (name "Net-(G1-XT2)") (class "Default")
      (node (ref "C20") (pin "1") (pinfunction "1_1") (pintype "passive"))
      (node (ref "G1") (pin "P$2") (pinfunction "XT2_P$2") (pintype "bidirectional"))
      (node (ref "U1") (pin "8") (pinfunction "PB7(XTAL2/TOSC2)_8") (pintype "bidirectional"))
    )
    (net (code "43") (name "Net-(IC1-REGIN)") (class "Default")
      (node (ref "C7") (pin "1") (pinfunction "1_1") (pintype "passive"))
      (node (ref "C8") (pin "1") (pinfunction "1_1") (pintype "passive"))
      (node (ref "IC1") (pin "7") (pinfunction "REGIN_7") (pintype "passive"))
      (node (ref "IC1") (pin "8") (pinfunction "VBUS_8") (pintype "input"))
      (node (ref "J2") (pin "A4B9") (pinfunction "VBUS_A4B9") (pintype "power_in"))
      (node (ref "J2") (pin "B4A9") (pinfunction "VBUS_B4A9") (pintype "power_in"))
    )
    (net (code "44") (name "Net-(IC1-VDD)") (class "Default")
      (node (ref "C5") (pin "1") (pinfunction "1_1") (pintype "passive"))
      (node (ref "C6") (pin "1") (pinfunction "1_1") (pintype "passive"))
      (node (ref "IC1") (pin "6") (pinfunction "VDD_6") (pintype "power_in"))
    )
    (net (code "45") (name "Net-(IC2-PadEN)") (class "Default")
      (node (ref "IC2") (pin "EN") (pinfunction "EN_EN") (pintype "bidirectional"))
      (node (ref "R20") (pin "1") (pinfunction "1_1") (pintype "passive"))
    )
    (net (code "46") (name "Net-(IC2-PadIO2)") (class "Default")
      (node (ref "IC2") (pin "IO2") (pinfunction "IO2_IO2") (pintype "bidirectional"))
      (node (ref "R15") (pin "2") (pinfunction "2_2") (pintype "passive"))
    )
    (net (code "47") (name "Net-(IC2-PadIO15)") (class "Default")
      (node (ref "IC2") (pin "IO15") (pinfunction "IO15_IO15") (pintype "bidirectional"))
      (node (ref "R16") (pin "2") (pinfunction "2_2") (pintype "passive"))
    )
    (net (code "48") (name "Net-(IC4-A)") (class "Default")
      (node (ref "ARD_UART") (pin "2") (pinfunction "2_2") (pintype "passive"))
      (node (ref "IC4") (pin "10") (pinfunction "A_10") (pintype "input"))
      (node (ref "R21") (pin "2") (pinfunction "2_2") (pintype "passive"))
    )
    (net (code "49") (name "Net-(IC4-B)") (class "Default")
      (node (ref "IC4") (pin "9") (pinfunction "B_9") (pintype "input"))
      (node (ref "R22") (pin "2") (pinfunction "2_2") (pintype "passive"))
    )
    (net (code "50") (name "Net-(J2-CC1)") (class "Default")
      (node (ref "J2") (pin "A5") (pinfunction "CC1_A5") (pintype "bidirectional"))
      (node (ref "R5") (pin "1") (pinfunction "1_1") (pintype "passive"))
    )
    (net (code "51") (name "Net-(J2-CC2)") (class "Default")
      (node (ref "J2") (pin "B5") (pinfunction "CC2_B5") (pintype "bidirectional"))
      (node (ref "R4") (pin "1") (pinfunction "1_1") (pintype "passive"))
    )
    (net (code "52") (name "Net-(LED-PadA)") (class "Default")
      (node (ref "LED") (pin "A") (pinfunction "A_A") (pintype "passive"))
      (node (ref "R18") (pin "2") (pinfunction "2_2") (pintype "passive"))
    )
    (net (code "53") (name "Net-(R29-Pad1)") (class "Default")
      (node (ref "R29") (pin "1") (pinfunction "1_1") (pintype "passive"))
      (node (ref "SD") (pin "A") (pinfunction "A_A") (pintype "passive"))
    )
    (net (code "54") (name "Net-(RTC1-OSCI)") (class "Default")
      (node (ref "C4") (pin "1") (pinfunction "1_1") (pintype "passive"))
      (node (ref "G2") (pin "2") (pinfunction "2_2") (pintype "bidirectional"))
      (node (ref "RTC1") (pin "1") (pinfunction "OSCI_1") (pintype "bidirectional"))
    )
    (net (code "55") (name "Net-(RTC1-OSCO)") (class "Default")
      (node (ref "C11") (pin "1") (pinfunction "1_1") (pintype "passive"))
      (node (ref "G2") (pin "1") (pinfunction "1_1") (pintype "bidirectional"))
      (node (ref "RTC1") (pin "2") (pinfunction "OSCO_2") (pintype "bidirectional"))
    )
    (net (code "56") (name "Net-(RTC1-VDD)") (class "Default")
      (node (ref "BT1") (pin "VDD") (pinfunction "VDD_VDD") (pintype "power_in"))
      (node (ref "BT1") (pin "VDD1") (pinfunction "VDD_VDD1") (pintype "power_in"))
      (node (ref "RTC1") (pin "8") (pinfunction "VDD_8") (pintype "bidirectional"))
    )
    (net (code "57") (name "Net-(VR1-VI)") (class "Default")
      (node (ref "C1") (pin "1") (pinfunction "1_1") (pintype "passive"))
      (node (ref "D2") (pin "C") (pinfunction "C_C") (pintype "passive"))
      (node (ref "VR1") (pin "1") (pinfunction "VI_1") (pintype "input"))
    )
    (net (code "58") (name "Net-(VR2-IN)") (class "Default")
      (node (ref "C10") (pin "+") (pinfunction "+_+") (pintype "passive"))
      (node (ref "D5") (pin "C") (pinfunction "C_C") (pintype "passive"))
      (node (ref "VR2") (pin "3") (pinfunction "IN_3") (pintype "input"))
    )
    (net (code "59") (name "RESET") (class "Default")
      (node (ref "C9") (pin "1") (pinfunction "1_1") (pintype "passive"))
      (node (ref "IC2") (pin "RST") (pinfunction "RST_RST") (pintype "input"))
      (node (ref "JP1") (pin "3") (pinfunction "3_3") (pintype "passive"))
      (node (ref "JP7") (pin "3") (pinfunction "3_3") (pintype "passive"))
      (node (ref "R1") (pin "2") (pinfunction "2_2") (pintype "passive"))
      (node (ref "RESET") (pin "C") (pinfunction "C_C") (pintype "bidirectional"))
      (node (ref "RESET") (pin "D") (pinfunction "C_D") (pintype "bidirectional"))
      (node (ref "U1") (pin "29") (pinfunction "PC6(/RESET)_29") (pintype "bidirectional"))
    )
    (net (code "60") (name "RTS") (class "Default")
      (node (ref "C9") (pin "2") (pinfunction "2_2") (pintype "passive"))
      (node (ref "IC1") (pin "24") (pinfunction "RTS_24") (pintype "output"))
      (node (ref "JP2") (pin "4") (pinfunction "4_4") (pintype "passive"))
    )
    (net (code "61") (name "RXI") (class "Default")
      (node (ref "IC1") (pin "26") (pinfunction "TXD_26") (pintype "output"))
      (node (ref "IC4") (pin "13") (pinfunction "X_13") (pintype "bidirectional"))
      (node (ref "JP2") (pin "3") (pinfunction "3_3") (pintype "passive"))
    )
    (net (code "62") (name "SCK") (class "Default")
      (node (ref "IC2") (pin "SCLK") (pinfunction "SCLK_SCLK") (pintype "bidirectional"))
      (node (ref "JP3") (pin "12") (pinfunction "12_12") (pintype "passive"))
      (node (ref "R18") (pin "1") (pinfunction "1_1") (pintype "passive"))
      (node (ref "SJ3") (pin "2") (pinfunction "2_2") (pintype "passive"))
      (node (ref "TF115") (pin "5") (pinfunction "CLK_5") (pintype "bidirectional"))
    )
    (net (code "63") (name "SCL") (class "Default")
      (node (ref "AS7262") (pin "P4") (pinfunction "4_P4") (pintype "bidirectional"))
      (node (ref "I2C_EXT") (pin "P4") (pinfunction "4_P4") (pintype "bidirectional"))
      (node (ref "JP6") (pin "1") (pinfunction "1_1") (pintype "passive"))
      (node (ref "R8") (pin "1") (pinfunction "1_1") (pintype "passive"))
      (node (ref "RTC1") (pin "6") (pinfunction "SCL_6") (pintype "bidirectional"))
      (node (ref "SCD30") (pin "P4") (pinfunction "4_P4") (pintype "bidirectional"))
      (node (ref "TSL2591") (pin "P4") (pinfunction "4_P4") (pintype "bidirectional"))
      (node (ref "U1") (pin "28") (pinfunction "PC5(ADC5/SCL)_28") (pintype "bidirectional"))
      (node (ref "VOC_DAT") (pin "P4") (pinfunction "4_P4") (pintype "bidirectional"))
    )
    (net (code "64") (name "SDA") (class "Default")
      (node (ref "AS7262") (pin "P3") (pinfunction "3_P3") (pintype "bidirectional"))
      (node (ref "I2C_EXT") (pin "P3") (pinfunction "3_P3") (pintype "bidirectional"))
      (node (ref "JP6") (pin "2") (pinfunction "2_2") (pintype "passive"))
      (node (ref "R7") (pin "1") (pinfunction "1_1") (pintype "passive"))
      (node (ref "RTC1") (pin "5") (pinfunction "SDA_5") (pintype "bidirectional"))
      (node (ref "SCD30") (pin "P3") (pinfunction "3_P3") (pintype "bidirectional"))
      (node (ref "TSL2591") (pin "P3") (pinfunction "3_P3") (pintype "bidirectional"))
      (node (ref "U1") (pin "27") (pinfunction "PC4(ADC4/SDA)_27") (pintype "bidirectional"))
      (node (ref "VOC_DAT") (pin "P3") (pinfunction "3_P3") (pintype "bidirectional"))
    )
    (net (code "65") (name "SD_CS") (class "Default")
      (node (ref "JP3") (pin "9") (pinfunction "9_9") (pintype "passive"))
      (node (ref "SD") (pin "C") (pinfunction "C_C") (pintype "passive"))
      (node (ref "TF115") (pin "2") (pinfunction "CD/DAT3_2") (pintype "bidirectional"))
      (node (ref "U1") (pin "14") (pinfunction "PB2(SS/OC1B)_14") (pintype "bidirectional"))
    )
    (net (code "66") (name "TXO") (class "Default")
      (node (ref "IC1") (pin "25") (pinfunction "RXD_25") (pintype "input"))
      (node (ref "IC4") (pin "3") (pinfunction "Y_3") (pintype "bidirectional"))
      (node (ref "JP2") (pin "2") (pinfunction "2_2") (pintype "passive"))
    )
    (net (code "67") (name "USBD+") (class "Default")
      (node (ref "IC1") (pin "4") (pinfunction "D+_4") (pintype "bidirectional"))
      (node (ref "J2") (pin "A6") (pinfunction "DP1_A6") (pintype "bidirectional"))
      (node (ref "J2") (pin "B6") (pinfunction "DP2_B6") (pintype "bidirectional"))
    )
    (net (code "68") (name "USBD-") (class "Default")
      (node (ref "IC1") (pin "5") (pinfunction "D-_5") (pintype "bidirectional"))
      (node (ref "J2") (pin "A7") (pinfunction "DN1_A7") (pintype "bidirectional"))
      (node (ref "J2") (pin "B7") (pinfunction "DN2_B7") (pintype "bidirectional"))
    )
    (net (code "69") (name "VIN") (class "Default")
      (node (ref "D2") (pin "A") (pinfunction "A_A") (pintype "passive"))
      (node (ref "D5") (pin "A") (pinfunction "A_A") (pintype "passive"))
      (node (ref "J1") (pin "3") (pinfunction "3_3") (pintype "passive"))
      (node (ref "JP7") (pin "1") (pinfunction "1_1") (pintype "passive"))
    )
    (net (code "70") (name "VOC_AUD") (class "Default")
      (node (ref "VOC_AE") (pin "P1") (pinfunction "1_P1") (pintype "bidirectional"))
    )
    (net (code "71") (name "VOC_EV") (class "Default")
      (node (ref "VOC_AE") (pin "P2") (pinfunction "2_P2") (pintype "bidirectional"))
    )
    (net (code "72") (name "unconnected-(IC1-CTS-Pad23)") (class "Default")
      (node (ref "IC1") (pin "23") (pinfunction "CTS_23") (pintype "input"))
    )
    (net (code "73") (name "unconnected-(IC1-DCD-Pad1)") (class "Default")
      (node (ref "IC1") (pin "1") (pinfunction "DCD_1") (pintype "input"))
    )
    (net (code "74") (name "unconnected-(IC1-DSR-Pad27)") (class "Default")
      (node (ref "IC1") (pin "27") (pinfunction "DSR_27") (pintype "input"))
    )
    (net (code "75") (name "unconnected-(IC1-RI-Pad2)") (class "Default")
      (node (ref "IC1") (pin "2") (pinfunction "RI_2") (pintype "input"))
    )
    (net (code "76") (name "unconnected-(IC1-SUSPEND-Pad12)") (class "Default")
      (node (ref "IC1") (pin "12") (pinfunction "SUSPEND_12") (pintype "output"))
    )
    (net (code "77") (name "unconnected-(IC1-~{RST}-Pad9)") (class "Default")
      (node (ref "IC1") (pin "9") (pinfunction "~{RST}_9") (pintype "bidirectional"))
    )
    (net (code "78") (name "unconnected-(IC1-~{SUSPEND}-Pad11)") (class "Default")
      (node (ref "IC1") (pin "11") (pinfunction "~{SUSPEND}_11") (pintype "output"))
    )
    (net (code "79") (name "unconnected-(IC4-X2-Pad15)") (class "Default")
      (node (ref "IC4") (pin "15") (pinfunction "X2_15") (pintype "bidirectional"))
    )
    (net (code "80") (name "unconnected-(IC4-X3-Pad11)") (class "Default")
      (node (ref "IC4") (pin "11") (pinfunction "X3_11") (pintype "bidirectional"))
    )
    (net (code "81") (name "unconnected-(IC4-Y2-Pad2)") (class "Default")
      (node (ref "IC4") (pin "2") (pinfunction "Y2_2") (pintype "bidirectional"))
    )
    (net (code "82") (name "unconnected-(IC4-Y3-Pad4)") (class "Default")
      (node (ref "IC4") (pin "4") (pinfunction "Y3_4") (pintype "bidirectional"))
    )
    (net (code "83") (name "unconnected-(J2-SBU1-PadA8)") (class "Default")
      (node (ref "J2") (pin "A8") (pinfunction "SBU1_A8") (pintype "bidirectional"))
    )
    (net (code "84") (name "unconnected-(J2-SBU2-PadB8)") (class "Default")
      (node (ref "J2") (pin "B8") (pinfunction "SBU2_B8") (pintype "bidirectional"))
    )
    (net (code "85") (name "unconnected-(MAX4466-4-PadP4)") (class "Default")
      (node (ref "MAX4466") (pin "P4") (pinfunction "4_P4") (pintype "bidirectional"))
    )
    (net (code "86") (name "unconnected-(MIX8410-Pad4)") (class "Default")
      (node (ref "MIX8410") (pin "4") (pinfunction "4_4") (pintype "passive"))
    )
    (net (code "87") (name "unconnected-(RTC1-CLKO-Pad7)") (class "Default")
      (node (ref "RTC1") (pin "7") (pinfunction "CLKO_7") (pintype "bidirectional"))
    )
    (net (code "88") (name "unconnected-(RTC1-{slash}INT-Pad3)") (class "Default")
      (node (ref "RTC1") (pin "3") (pinfunction "/INT_3") (pintype "bidirectional"))
    )
    (net (code "89") (name "unconnected-(TF115-DAT1-Pad8)") (class "Default")
      (node (ref "TF115") (pin "8") (pinfunction "DAT1_8") (pintype "bidirectional"))
    )
    (net (code "90") (name "unconnected-(TF115-DAT2-Pad1)") (class "Default")
      (node (ref "TF115") (pin "1") (pinfunction "DAT2_1") (pintype "bidirectional"))
    )
    (net (code "91") (name "unconnected-(VOC_AE-4-PadP4)") (class "Default")
      (node (ref "VOC_AE") (pin "P4") (pinfunction "4_P4") (pintype "bidirectional"))
    )
  )
)
